# st_link.net
KiCad netlist of a schematic drawn in Altium Designer
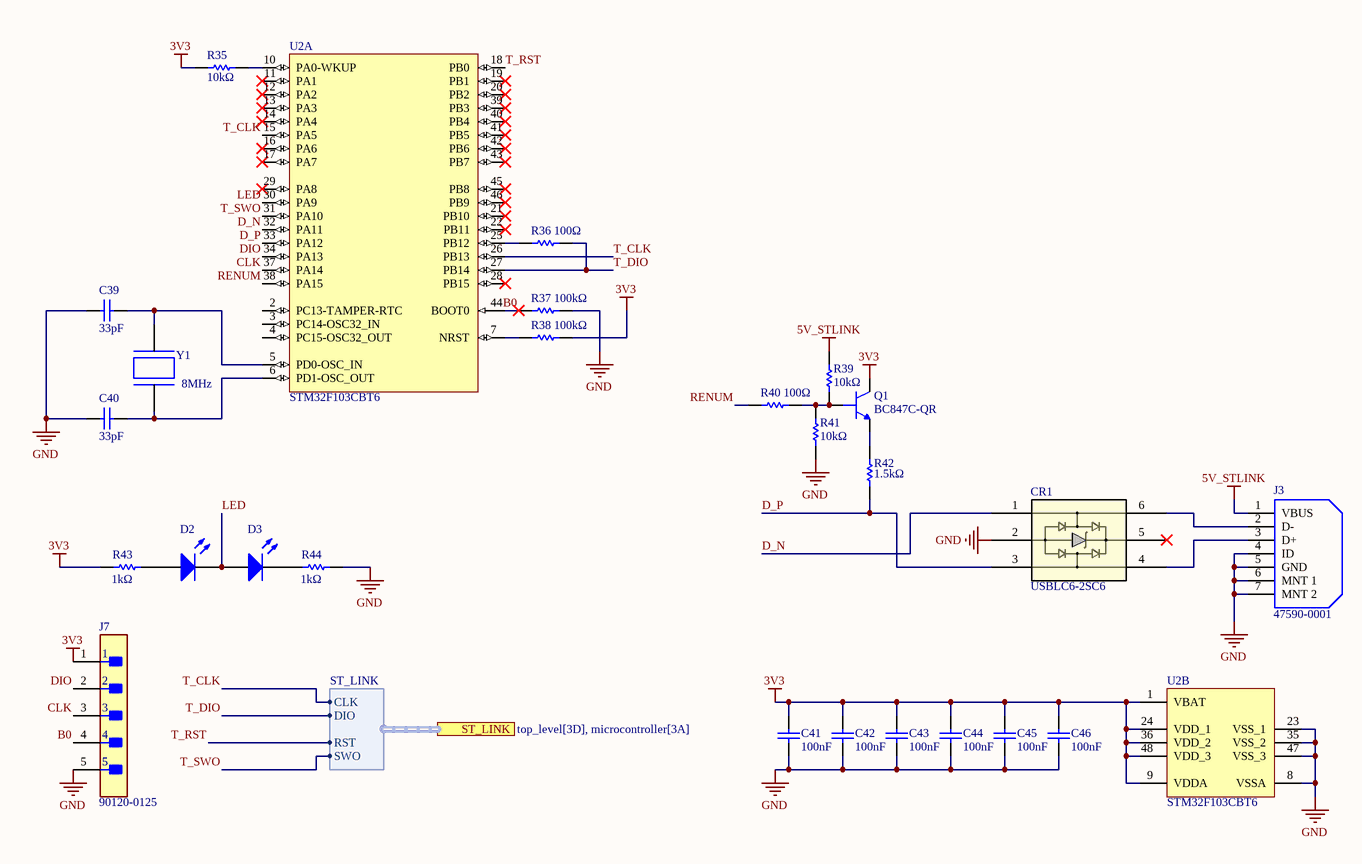
[diagram p0: st_link.SchDoc]

(export (version "E")
  (design (tool "Eeschema 10.0.6"))
  (components
    (comp (ref "C39")
      (value "33pF")
      (footprint "C0603")
      (description "0603 33 pF 50 V ±5 % Tolerance C0G/NP0 SMT Multilayer Ceramic Capacitor")
      (fields (field (name "TOLERANCE") "5%") (field (name "Comment") "CC0603JPNPO9BN330"))
      (libsource (lib "Sunswift Racing") (part "Capacitor"))
    )
    (comp (ref "C40")
      (value "33pF")
      (footprint "C0603")
      (description "0603 33 pF 50 V ±5 % Tolerance C0G/NP0 SMT Multilayer Ceramic Capacitor")
      (fields (field (name "TOLERANCE") "5%") (field (name "Comment") "CC0603JPNPO9BN330"))
      (libsource (lib "Sunswift Racing") (part "Capacitor"))
    )
    (comp (ref "C41")
      (value "100nF")
      (footprint "C0603")
      (description "25V 100nF X7R ±10% 0603 Multilayer Ceramic Capacitors MLCC - SMD/SMT ROHS")
      (fields (field (name "TOLERANCE") "10%") (field (name "VOLTAGE") "25V"))
      (libsource (lib "Sunswift Racing") (part "Capacitor"))
    )
    (comp (ref "C42")
      (value "100nF")
      (footprint "C0603")
      (description "25V 100nF X7R ±10% 0603 Multilayer Ceramic Capacitors MLCC - SMD/SMT ROHS")
      (fields (field (name "TOLERANCE") "10%") (field (name "VOLTAGE") "25V"))
      (libsource (lib "Sunswift Racing") (part "Capacitor"))
    )
    (comp (ref "C43")
      (value "100nF")
      (footprint "C0603")
      (description "25V 100nF X7R ±10% 0603 Multilayer Ceramic Capacitors MLCC - SMD/SMT ROHS")
      (fields (field (name "TOLERANCE") "10%") (field (name "VOLTAGE") "25V"))
      (libsource (lib "Sunswift Racing") (part "Capacitor"))
    )
    (comp (ref "C44")
      (value "100nF")
      (footprint "C0603")
      (description "25V 100nF X7R ±10% 0603 Multilayer Ceramic Capacitors MLCC - SMD/SMT ROHS")
      (fields (field (name "TOLERANCE") "10%") (field (name "VOLTAGE") "25V"))
      (libsource (lib "Sunswift Racing") (part "Capacitor"))
    )
    (comp (ref "C45")
      (value "100nF")
      (footprint "C0603")
      (description "25V 100nF X7R ±10% 0603 Multilayer Ceramic Capacitors MLCC - SMD/SMT ROHS")
      (fields (field (name "TOLERANCE") "10%") (field (name "VOLTAGE") "25V"))
      (libsource (lib "Sunswift Racing") (part "Capacitor"))
    )
    (comp (ref "C46")
      (value "100nF")
      (footprint "C0603")
      (description "25V 100nF X7R ±10% 0603 Multilayer Ceramic Capacitors MLCC - SMD/SMT ROHS")
      (fields (field (name "TOLERANCE") "10%") (field (name "VOLTAGE") "25V"))
      (libsource (lib "Sunswift Racing") (part "Capacitor"))
    )
    (comp (ref "CR1")
      (value "USBLC6-2SC6")
      (footprint "SOT23-6L_STM")
      (description "ESD Protection for USB 2.0 High Speed")
      (fields (field (name "COPYRIGHT") "Copyright (C) 2025 Ultra Librarian. All rights reserved."))
      (libsource (lib "Sunswift Racing") (part "USBLC6-2SC6"))
    )
    (comp (ref "D2")
      (value "LED EMERALD 0805")
      (footprint "0805 LED")
      (description "Emerald 0805  Light Emitting Diodes (LED) ROHS GREEN JLCPCB PICK&PLACE")
      (fields (field (name "MFR.PART #") "C2297") (field (name "MANUFACTURER") "Hubei KENTO Elec"))
      (libsource (lib "Sunswift Racing") (part "LED 0805-Symbol-1"))
    )
    (comp (ref "D3")
      (value "LED RED 0805")
      (footprint "0805 LED")
      (description "Red 0805  Light Emitting Diodes (LED) ROHS JLCPCB PICK&PLACE")
      (fields
        (field (name "MANUFACTURER") "Foshan NationStar Optoelectronics")
        (field (name "JLCPCB PART #") "C84256")
      )
      (libsource (lib "Sunswift Racing") (part "LED 0805-Symbol-1"))
    )
    (comp (ref "J3")
      (value "47590-0001")
      (footprint "USB")
      (fields
        (field (name "JLCPCB PART #") "C136001")
        (field (name "MANUFACTURER") "MOLEX")
        (field (name "MFR.PART #") "475900001")
        (field (name "SOURCE") "https://jlcpcb.com/partdetail/Molex-475900001/C136001")
      )
      (libsource (lib "Sunswift Racing") (part "bfe7818bcc57c6509ae19e185e1eba7"))
    )
    (comp (ref "J7")
      (value "90120-0125")
      (footprint "FP-90120-0125-MFG")
      (libsource (lib "Sunswift Racing") (part "bf93c07fd2649a848d0ec8585582aab"))
    )
    (comp (ref "Q1")
      (value "BC847C-QR")
      (footprint "TO-236AB-3")
      (description "NPN general-purpose transistors in a small SOT23 (TO-236AB) Surface-Mounted Device (SMD)")
      (fields (field (name "JLCPCB PART #") "C5336792"))
      (libsource (lib "Sunswift Racing") (part "BJT_NPN"))
    )
    (comp (ref "R35")
      (value "10kΩ")
      (footprint "RESC1608X55X25ML10T15")
      (description "10 kOhms ±1% 0.1W, 1/10W Chip Resistor 0603 (1608 Metric) Moisture Resistant Thick Film")
      (fields (field (name "TOLERANCE") "1%") (field (name "Comment") "RC0603FR-0710KL"))
      (libsource (lib "Sunswift Racing") (part "RES-2"))
    )
    (comp (ref "R36")
      (value "100Ω")
      (footprint "RESC1608X55X25ML10T15")
      (description "Yageo RC0603FR-07100RL 0603 SMD Resistor 100 Ohm thin film chip resistor")
      (fields (field (name "TOLERANCE") "1%") (field (name "Comment") "RC0603FR-07100RL"))
      (libsource (lib "Sunswift Racing") (part "RES-2"))
    )
    (comp (ref "R37")
      (value "100kΩ")
      (footprint "RESC1608X55X25ML10T15")
      (description "Res General Purpose Thick Film 0603 100k Ohm 1% 1/10W ±100ppm/°C Molded Paper T/R")
      (fields (field (name "TOLERANCE") "1%") (field (name "Comment") "RC0603FR-07100KL"))
      (libsource (lib "Sunswift Racing") (part "RES-2"))
    )
    (comp (ref "R38")
      (value "100kΩ")
      (footprint "RESC1608X55X25ML10T15")
      (description "Res General Purpose Thick Film 0603 100k Ohm 1% 1/10W ±100ppm/°C Molded Paper T/R")
      (fields (field (name "TOLERANCE") "1%") (field (name "Comment") "RC0603FR-07100KL"))
      (libsource (lib "Sunswift Racing") (part "RES-2"))
    )
    (comp (ref "R39")
      (value "10kΩ")
      (footprint "RESC1608X55X25ML10T15")
      (description "10 kOhms ±1% 0.1W, 1/10W Chip Resistor 0603 (1608 Metric) Moisture Resistant Thick Film")
      (fields (field (name "TOLERANCE") "1%") (field (name "Comment") "RC0603FR-0710KL"))
      (libsource (lib "Sunswift Racing") (part "RES-2"))
    )
    (comp (ref "R40")
      (value "100Ω")
      (footprint "RESC1608X55X25ML10T15")
      (description "Yageo RC0603FR-07100RL 0603 SMD Resistor 100 Ohm thin film chip resistor")
      (fields (field (name "TOLERANCE") "1%") (field (name "Comment") "RC0603FR-07100RL"))
      (libsource (lib "Sunswift Racing") (part "RES-2"))
    )
    (comp (ref "R41")
      (value "10kΩ")
      (footprint "RESC1608X55X25ML10T15")
      (description "10 kOhms ±1% 0.1W, 1/10W Chip Resistor 0603 (1608 Metric) Moisture Resistant Thick Film")
      (fields (field (name "TOLERANCE") "1%") (field (name "Comment") "RC0603FR-0710KL"))
      (libsource (lib "Sunswift Racing") (part "RES-2"))
    )
    (comp (ref "R42")
      (value "1.5kΩ")
      (footprint "RESC1608X55X25ML10T15")
      (description "Res General Purpose Thick Film 0603 1.5k Ohm 5% 1/10W ±100ppm/°C Molded Paper T/R")
      (fields (field (name "TOLERANCE") "5%") (field (name "Comment") "RC0603JR-071K5L"))
      (libsource (lib "Sunswift Racing") (part "RES-2"))
    )
    (comp (ref "R43")
      (value "1kΩ")
      (footprint "RESC1608X55X25ML10T15")
      (description "1 kOhms ±1% 0.1W, 1/10W Chip Resistor 0603 (1608 Metric) Moisture Resistant Thick Film")
      (fields (field (name "TOLERANCE") "1%") (field (name "Comment") "RC0603FR-101KL"))
      (libsource (lib "Sunswift Racing") (part "RES-2"))
    )
    (comp (ref "R44")
      (value "1kΩ")
      (footprint "RESC1608X55X25ML10T15")
      (description "1 kOhms ±1% 0.1W, 1/10W Chip Resistor 0603 (1608 Metric) Moisture Resistant Thick Film")
      (fields (field (name "TOLERANCE") "1%") (field (name "Comment") "RC0603FR-101KL"))
      (libsource (lib "Sunswift Racing") (part "RES-2"))
    )
    (comp (ref "U2")
      (value "STM32F103CBT6")
      (footprint "STM-LQFP48_N")
      (description "RISC Microcontroller, 32-Bit, FLASH, CORTEX-M3 CPU, 72MHz, CMOS, PQFP48")
      (fields (field (name "JLCPCB PART #") "C8304"))
      (libsource (lib "Sunswift Racing") (part "MC-ARM-STM32F103X8_B-SQ48"))
    )
    (comp (ref "Y1")
      (value "X50328MSB2GI")
      (footprint "RESC5032X135N")
      (description "8MHz 20pF ±10ppm SMD5032-2P Crystals ROHS JLCPCB PICK&PLACE")
      (fields
        (field (name "MANUFACTURER") "Yangxing Tech")
        (field (name "JLCPCB PART #") "C115962")
        (field (name "FREQUENCY") "8MHz")
      )
      (libsource (lib "Sunswift Racing") (part "X50328MSB2GI-Symbol-1"))
    )
  )
  (nets
    (net (code "2") (name "/B0") (class "Default")
      (node (ref "J7") (pin "4") (pinfunction "4_4") (pintype "passive"))
      (node (ref "R37") (pin "1") (pinfunction "1_1") (pintype "passive"))
      (node (ref "U2") (pin "44") (pinfunction "BOOT0_44") (pintype "input"))
    )
    (net (code "3") (name "/CLK") (class "Default")
      (node (ref "J7") (pin "3") (pinfunction "3_3") (pintype "passive"))
      (node (ref "U2") (pin "37") (pinfunction "PA14_37") (pintype "bidirectional"))
    )
    (net (code "4") (name "/DIO") (class "Default")
      (node (ref "J7") (pin "2") (pinfunction "2_2") (pintype "passive"))
      (node (ref "U2") (pin "34") (pinfunction "PA13_34") (pintype "bidirectional"))
    )
    (net (code "5") (name "/D_N") (class "Default")
      (node (ref "CR1") (pin "1") (pinfunction "1_1") (pintype "passive"))
      (node (ref "U2") (pin "32") (pinfunction "PA11_32") (pintype "bidirectional"))
    )
    (net (code "6") (name "/D_P") (class "Default")
      (node (ref "CR1") (pin "3") (pinfunction "3_3") (pintype "passive"))
      (node (ref "R42") (pin "1") (pinfunction "1_1") (pintype "passive"))
      (node (ref "U2") (pin "33") (pinfunction "PA12_33") (pintype "bidirectional"))
    )
    (net (code "7") (name "/LED") (class "Default")
      (node (ref "D2") (pin "K") (pinfunction "K_K") (pintype "passive"))
      (node (ref "D3") (pin "A") (pinfunction "A_A") (pintype "passive"))
      (node (ref "U2") (pin "30") (pinfunction "PA9_30") (pintype "bidirectional"))
    )
    (net (code "8") (name "/RENUM") (class "Default")
      (node (ref "R40") (pin "1") (pinfunction "1_1") (pintype "passive"))
      (node (ref "U2") (pin "38") (pinfunction "PA15_38") (pintype "bidirectional"))
    )
    (net (code "9") (name "/T_CLK") (class "Default")
      (node (ref "U2") (pin "15") (pinfunction "PA5_15") (pintype "bidirectional"))
      (node (ref "U2") (pin "26") (pinfunction "PB13_26") (pintype "bidirectional"))
    )
    (net (code "10") (name "/T_DIO") (class "Default")
      (node (ref "R36") (pin "2") (pinfunction "2_2") (pintype "passive"))
      (node (ref "U2") (pin "27") (pinfunction "PB14_27") (pintype "bidirectional"))
    )
    (net (code "11") (name "/T_RST") (class "Default")
      (node (ref "U2") (pin "18") (pinfunction "PB0_18") (pintype "bidirectional"))
    )
    (net (code "12") (name "/T_SWO") (class "Default")
      (node (ref "U2") (pin "31") (pinfunction "PA10_31") (pintype "bidirectional"))
    )
    (net (code "14") (name "3V3") (class "Default")
      (node (ref "C41") (pin "2") (pinfunction "2_2") (pintype "passive"))
      (node (ref "C42") (pin "2") (pinfunction "2_2") (pintype "passive"))
      (node (ref "C43") (pin "2") (pinfunction "2_2") (pintype "passive"))
      (node (ref "C44") (pin "2") (pinfunction "2_2") (pintype "passive"))
      (node (ref "C45") (pin "2") (pinfunction "2_2") (pintype "passive"))
      (node (ref "C46") (pin "2") (pinfunction "2_2") (pintype "passive"))
      (node (ref "J7") (pin "1") (pinfunction "1_1") (pintype "passive"))
      (node (ref "Q1") (pin "3") (pinfunction "Collector_3") (pintype "passive"))
      (node (ref "R35") (pin "2") (pinfunction "2_2") (pintype "passive"))
      (node (ref "R38") (pin "2") (pinfunction "2_2") (pintype "passive"))
      (node (ref "R43") (pin "1") (pinfunction "1_1") (pintype "passive"))
      (node (ref "U2") (pin "1") (pinfunction "VBAT_1") (pintype "power_in"))
      (node (ref "U2") (pin "24") (pinfunction "VDD_1_24") (pintype "power_in"))
      (node (ref "U2") (pin "36") (pinfunction "VDD_2_36") (pintype "power_in"))
      (node (ref "U2") (pin "48") (pinfunction "VDD_3_48") (pintype "power_in"))
      (node (ref "U2") (pin "9") (pinfunction "VDDA_9") (pintype "power_in"))
    )
    (net (code "15") (name "5V_STLINK") (class "Default")
      (node (ref "J3") (pin "1") (pinfunction "VBUS_1") (pintype "passive"))
      (node (ref "R39") (pin "1") (pinfunction "1_1") (pintype "passive"))
    )
    (net (code "16") (name "GND") (class "Default")
      (node (ref "C39") (pin "1") (pinfunction "1_1") (pintype "passive"))
      (node (ref "C40") (pin "2") (pinfunction "2_2") (pintype "passive"))
      (node (ref "C41") (pin "1") (pinfunction "1_1") (pintype "passive"))
      (node (ref "C42") (pin "1") (pinfunction "1_1") (pintype "passive"))
      (node (ref "C43") (pin "1") (pinfunction "1_1") (pintype "passive"))
      (node (ref "C44") (pin "1") (pinfunction "1_1") (pintype "passive"))
      (node (ref "C45") (pin "1") (pinfunction "1_1") (pintype "passive"))
      (node (ref "C46") (pin "1") (pinfunction "1_1") (pintype "passive"))
      (node (ref "CR1") (pin "2") (pinfunction "2_2") (pintype "passive"))
      (node (ref "J3") (pin "4") (pinfunction "ID_4") (pintype "passive"))
      (node (ref "J3") (pin "5") (pinfunction "GND_5") (pintype "passive"))
      (node (ref "J3") (pin "6") (pinfunction "MNT_1_6") (pintype "passive"))
      (node (ref "J3") (pin "7") (pinfunction "MNT_2_7") (pintype "passive"))
      (node (ref "J7") (pin "5") (pinfunction "5_5") (pintype "passive"))
      (node (ref "R37") (pin "2") (pinfunction "2_2") (pintype "passive"))
      (node (ref "R41") (pin "2") (pinfunction "2_2") (pintype "passive"))
      (node (ref "R44") (pin "2") (pinfunction "2_2") (pintype "passive"))
      (node (ref "U2") (pin "23") (pinfunction "VSS_1_23") (pintype "power_in"))
      (node (ref "U2") (pin "35") (pinfunction "VSS_2_35") (pintype "power_in"))
      (node (ref "U2") (pin "47") (pinfunction "VSS_3_47") (pintype "power_in"))
      (node (ref "U2") (pin "8") (pinfunction "VSSA_8") (pintype "power_in"))
    )
    (net (code "17") (name "Net-(D2-PadA)") (class "Default")
      (node (ref "D2") (pin "A") (pinfunction "A_A") (pintype "passive"))
      (node (ref "R43") (pin "2") (pinfunction "2_2") (pintype "passive"))
    )
    (net (code "18") (name "Net-(D3-PadK)") (class "Default")
      (node (ref "D3") (pin "K") (pinfunction "K_K") (pintype "passive"))
      (node (ref "R44") (pin "1") (pinfunction "1_1") (pintype "passive"))
    )
    (net (code "19") (name "Net-(J3-D+)") (class "Default")
      (node (ref "CR1") (pin "4") (pinfunction "4_4") (pintype "passive"))
      (node (ref "J3") (pin "3") (pinfunction "D+_3") (pintype "passive"))
    )
    (net (code "20") (name "Net-(J3-D-)") (class "Default")
      (node (ref "CR1") (pin "6") (pinfunction "6_6") (pintype "passive"))
      (node (ref "J3") (pin "2") (pinfunction "D-_2") (pintype "passive"))
    )
    (net (code "21") (name "Net-(Q1-Base)") (class "Default")
      (node (ref "Q1") (pin "1") (pinfunction "Base_1") (pintype "passive"))
      (node (ref "R39") (pin "2") (pinfunction "2_2") (pintype "passive"))
      (node (ref "R40") (pin "2") (pinfunction "2_2") (pintype "passive"))
      (node (ref "R41") (pin "1") (pinfunction "1_1") (pintype "passive"))
    )
    (net (code "22") (name "Net-(Q1-Emitter)") (class "Default")
      (node (ref "Q1") (pin "2") (pinfunction "Emitter_2") (pintype "passive"))
      (node (ref "R42") (pin "2") (pinfunction "2_2") (pintype "passive"))
    )
    (net (code "23") (name "Net-(U2A-NRST)") (class "Default")
      (node (ref "R38") (pin "1") (pinfunction "1_1") (pintype "passive"))
      (node (ref "U2") (pin "7") (pinfunction "NRST_7") (pintype "bidirectional"))
    )
    (net (code "24") (name "Net-(U2A-PA0-WKUP)") (class "Default")
      (node (ref "R35") (pin "1") (pinfunction "1_1") (pintype "passive"))
      (node (ref "U2") (pin "10") (pinfunction "PA0-WKUP_10") (pintype "bidirectional"))
    )
    (net (code "25") (name "Net-(U2A-PB12)") (class "Default")
      (node (ref "R36") (pin "1") (pinfunction "1_1") (pintype "passive"))
      (node (ref "U2") (pin "25") (pinfunction "PB12_25") (pintype "bidirectional"))
    )
    (net (code "26") (name "Net-(U2A-PD0-OSC_IN)") (class "Default")
      (node (ref "C39") (pin "2") (pinfunction "2_2") (pintype "passive"))
      (node (ref "U2") (pin "5") (pinfunction "PD0-OSC_IN_5") (pintype "bidirectional"))
      (node (ref "Y1") (pin "2") (pinfunction "2_2") (pintype "passive"))
    )
    (net (code "27") (name "Net-(U2A-PD1-OSC_OUT)") (class "Default")
      (node (ref "C40") (pin "1") (pinfunction "1_1") (pintype "passive"))
      (node (ref "U2") (pin "6") (pinfunction "PD1-OSC_OUT_6") (pintype "bidirectional"))
      (node (ref "Y1") (pin "1") (pinfunction "1_1") (pintype "passive"))
    )
    (net (code "28") (name "unconnected-(CR1-Pad5)") (class "Default")
      (node (ref "CR1") (pin "5") (pinfunction "5_5") (pintype "passive+no_connect"))
    )
    (net (code "29") (name "unconnected-(U2A-PA1-Pad11)") (class "Default")
      (node (ref "U2") (pin "11") (pinfunction "PA1_11") (pintype "bidirectional+no_connect"))
    )
    (net (code "30") (name "unconnected-(U2A-PA2-Pad12)") (class "Default")
      (node (ref "U2") (pin "12") (pinfunction "PA2_12") (pintype "bidirectional+no_connect"))
    )
    (net (code "31") (name "unconnected-(U2A-PA3-Pad13)") (class "Default")
      (node (ref "U2") (pin "13") (pinfunction "PA3_13") (pintype "bidirectional+no_connect"))
    )
    (net (code "32") (name "unconnected-(U2A-PA4-Pad14)") (class "Default")
      (node (ref "U2") (pin "14") (pinfunction "PA4_14") (pintype "bidirectional+no_connect"))
    )
    (net (code "33") (name "unconnected-(U2A-PA6-Pad16)") (class "Default")
      (node (ref "U2") (pin "16") (pinfunction "PA6_16") (pintype "bidirectional+no_connect"))
    )
    (net (code "34") (name "unconnected-(U2A-PA7-Pad17)") (class "Default")
      (node (ref "U2") (pin "17") (pinfunction "PA7_17") (pintype "bidirectional+no_connect"))
    )
    (net (code "35") (name "unconnected-(U2A-PA8-Pad29)") (class "Default")
      (node (ref "U2") (pin "29") (pinfunction "PA8_29") (pintype "bidirectional+no_connect"))
    )
    (net (code "36") (name "unconnected-(U2A-PB1-Pad19)") (class "Default")
      (node (ref "U2") (pin "19") (pinfunction "PB1_19") (pintype "bidirectional+no_connect"))
    )
    (net (code "37") (name "unconnected-(U2A-PB2-Pad20)") (class "Default")
      (node (ref "U2") (pin "20") (pinfunction "PB2_20") (pintype "bidirectional+no_connect"))
    )
    (net (code "38") (name "unconnected-(U2A-PB3-Pad39)") (class "Default")
      (node (ref "U2") (pin "39") (pinfunction "PB3_39") (pintype "bidirectional+no_connect"))
    )
    (net (code "39") (name "unconnected-(U2A-PB4-Pad40)") (class "Default")
      (node (ref "U2") (pin "40") (pinfunction "PB4_40") (pintype "bidirectional+no_connect"))
    )
    (net (code "40") (name "unconnected-(U2A-PB5-Pad41)") (class "Default")
      (node (ref "U2") (pin "41") (pinfunction "PB5_41") (pintype "bidirectional+no_connect"))
    )
    (net (code "41") (name "unconnected-(U2A-PB6-Pad42)") (class "Default")
      (node (ref "U2") (pin "42") (pinfunction "PB6_42") (pintype "bidirectional+no_connect"))
    )
    (net (code "42") (name "unconnected-(U2A-PB7-Pad43)") (class "Default")
      (node (ref "U2") (pin "43") (pinfunction "PB7_43") (pintype "bidirectional+no_connect"))
    )
    (net (code "43") (name "unconnected-(U2A-PB8-Pad45)") (class "Default")
      (node (ref "U2") (pin "45") (pinfunction "PB8_45") (pintype "bidirectional+no_connect"))
    )
    (net (code "44") (name "unconnected-(U2A-PB9-Pad46)") (class "Default")
      (node (ref "U2") (pin "46") (pinfunction "PB9_46") (pintype "bidirectional+no_connect"))
    )
    (net (code "45") (name "unconnected-(U2A-PB10-Pad21)") (class "Default")
      (node (ref "U2") (pin "21") (pinfunction "PB10_21") (pintype "bidirectional+no_connect"))
    )
    (net (code "46") (name "unconnected-(U2A-PB11-Pad22)") (class "Default")
      (node (ref "U2") (pin "22") (pinfunction "PB11_22") (pintype "bidirectional+no_connect"))
    )
    (net (code "47") (name "unconnected-(U2A-PB15-Pad28)") (class "Default")
      (node (ref "U2") (pin "28") (pinfunction "PB15_28") (pintype "bidirectional+no_connect"))
    )
    (net (code "48") (name "unconnected-(U2A-PC13-TAMPER-RTC-Pad2)") (class "Default")
      (node (ref "U2") (pin "2") (pinfunction "PC13-TAMPER-RTC_2") (pintype "bidirectional"))
    )
    (net (code "49") (name "unconnected-(U2A-PC14-OSC32_IN-Pad3)") (class "Default")
      (node (ref "U2") (pin "3") (pinfunction "PC14-OSC32_IN_3") (pintype "bidirectional"))
    )
    (net (code "50") (name "unconnected-(U2A-PC15-OSC32_OUT-Pad4)") (class "Default")
      (node (ref "U2") (pin "4") (pinfunction "PC15-OSC32_OUT_4") (pintype "bidirectional"))
    )
  )
)
